# Filter-PCB.net
KiCad netlist of a schematic drawn in EAGLE
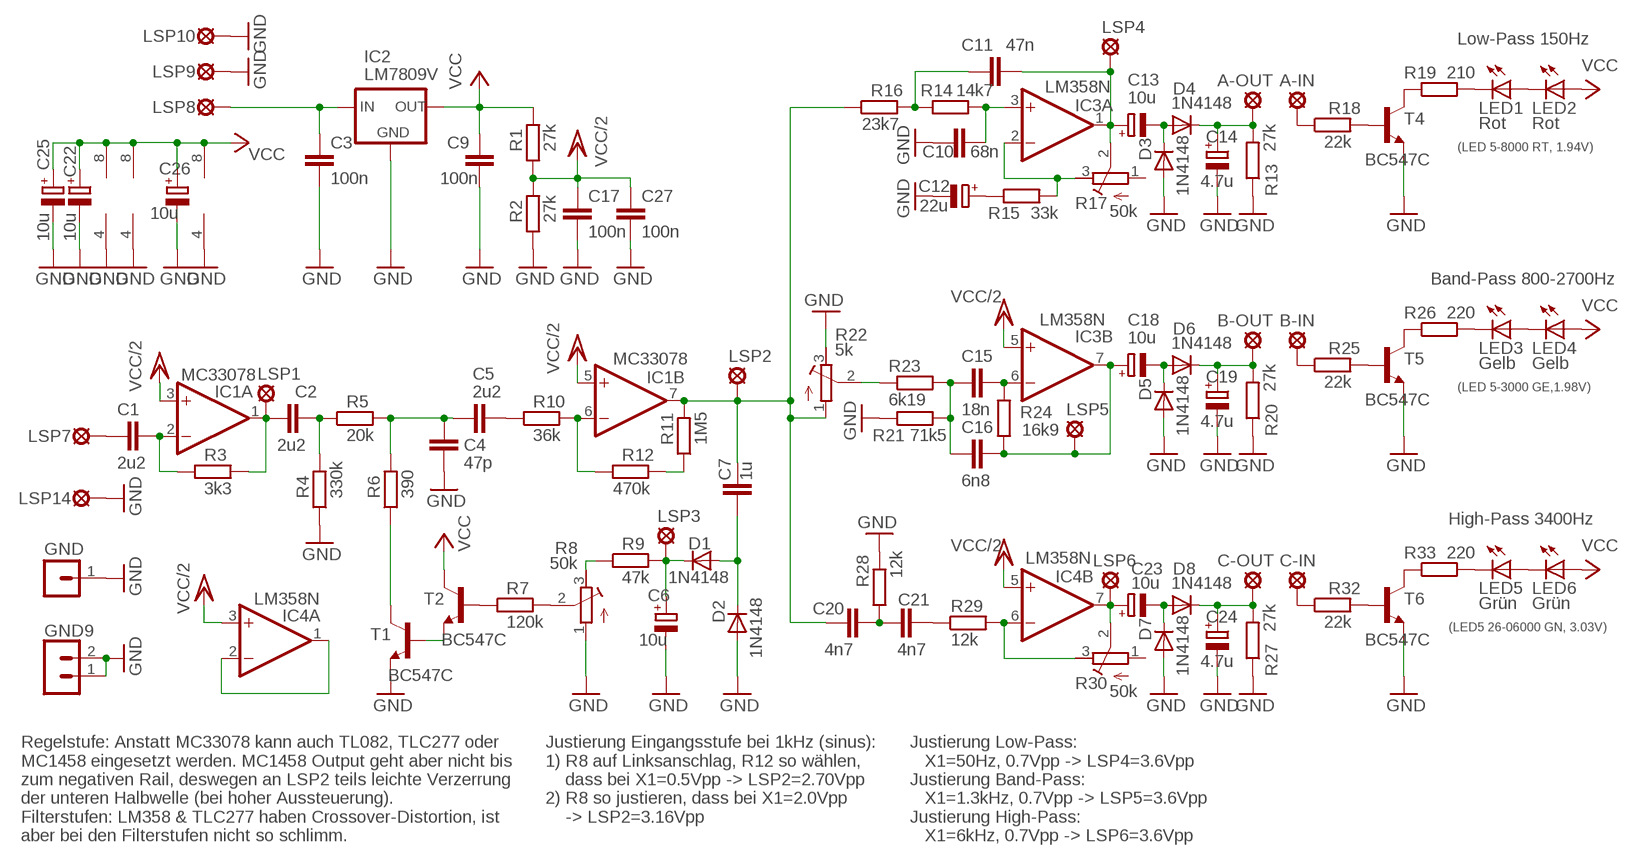
[diagram p0: schematic, sheet 1]

(export (version "E")
  (design (tool "Eeschema 10.0.6"))
  (components
    (comp (ref "A-IN")
      (value "LSP13")
      (footprint "eagle-import:LSP13")
      (libsource (lib "eagle-import") (part "LSP13"))
    )
    (comp (ref "A-OUT")
      (value "LSP13")
      (footprint "eagle-import:LSP13")
      (libsource (lib "eagle-import") (part "LSP13"))
    )
    (comp (ref "B-IN")
      (value "LSP13")
      (footprint "eagle-import:LSP13")
      (libsource (lib "eagle-import") (part "LSP13"))
    )
    (comp (ref "B-OUT")
      (value "LSP13")
      (footprint "eagle-import:LSP13")
      (libsource (lib "eagle-import") (part "LSP13"))
    )
    (comp (ref "C-IN")
      (value "LSP13")
      (footprint "eagle-import:LSP13")
      (libsource (lib "eagle-import") (part "LSP13"))
    )
    (comp (ref "C-OUT")
      (value "LSP13")
      (footprint "eagle-import:LSP13")
      (libsource (lib "eagle-import") (part "LSP13"))
    )
    (comp (ref "C1")
      (value "2u2")
      (footprint "eagle-import:C1206")
      (libsource (lib "eagle-import") (part "C-EUC1206"))
    )
    (comp (ref "C2")
      (value "2u2")
      (footprint "eagle-import:C1206")
      (libsource (lib "eagle-import") (part "C-EUC1206"))
    )
    (comp (ref "C3")
      (value "100n")
      (footprint "eagle-import:C050-024X044")
      (libsource (lib "eagle-import") (part "C-EU050-024X044"))
    )
    (comp (ref "C4")
      (value "47p")
      (footprint "eagle-import:C1206")
      (libsource (lib "eagle-import") (part "C-EUC1206"))
    )
    (comp (ref "C5")
      (value "2u2")
      (footprint "eagle-import:C1206")
      (libsource (lib "eagle-import") (part "C-EUC1206"))
    )
    (comp (ref "C6")
      (value "10u")
      (footprint "eagle-import:TT2D4")
      (libsource (lib "eagle-import") (part "CPOL-EUTT2D4"))
    )
    (comp (ref "C7")
      (value "1u")
      (footprint "eagle-import:C050-024X044")
      (libsource (lib "eagle-import") (part "C-EU050-024X044"))
    )
    (comp (ref "C9")
      (value "100n")
      (footprint "eagle-import:C1206")
      (libsource (lib "eagle-import") (part "C-EUC1206"))
    )
    (comp (ref "C10")
      (value "68n")
      (footprint "eagle-import:C1206")
      (libsource (lib "eagle-import") (part "C-EUC1206"))
    )
    (comp (ref "C11")
      (value "47n")
      (footprint "eagle-import:C1206")
      (libsource (lib "eagle-import") (part "C-EUC1206"))
    )
    (comp (ref "C12")
      (value "22u")
      (footprint "eagle-import:TT2D4")
      (libsource (lib "eagle-import") (part "CPOL-EUTT2D4"))
    )
    (comp (ref "C13")
      (value "10u")
      (footprint "eagle-import:TT2D4")
      (libsource (lib "eagle-import") (part "CPOL-EUTT2D4"))
    )
    (comp (ref "C14")
      (value "4.7u")
      (footprint "eagle-import:TT2D4")
      (libsource (lib "eagle-import") (part "CPOL-EUTT2D4"))
    )
    (comp (ref "C15")
      (value "18n")
      (footprint "eagle-import:C1206")
      (libsource (lib "eagle-import") (part "C-EUC1206"))
    )
    (comp (ref "C16")
      (value "6n8")
      (footprint "eagle-import:C1206")
      (libsource (lib "eagle-import") (part "C-EUC1206"))
    )
    (comp (ref "C17")
      (value "100n")
      (footprint "eagle-import:C050-024X044")
      (libsource (lib "eagle-import") (part "C-EU050-024X044"))
    )
    (comp (ref "C18")
      (value "10u")
      (footprint "eagle-import:TT2D4")
      (libsource (lib "eagle-import") (part "CPOL-EUTT2D4"))
    )
    (comp (ref "C19")
      (value "4.7u")
      (footprint "eagle-import:TT2D4")
      (libsource (lib "eagle-import") (part "CPOL-EUTT2D4"))
    )
    (comp (ref "C20")
      (value "4n7")
      (footprint "eagle-import:C050-024X044")
      (libsource (lib "eagle-import") (part "C-EU050-024X044"))
    )
    (comp (ref "C21")
      (value "4n7")
      (footprint "eagle-import:C050-024X044")
      (libsource (lib "eagle-import") (part "C-EU050-024X044"))
    )
    (comp (ref "C22")
      (value "10u")
      (footprint "eagle-import:TT2D4")
      (libsource (lib "eagle-import") (part "CPOL-EUTT2D4"))
    )
    (comp (ref "C23")
      (value "10u")
      (footprint "eagle-import:TT2D4")
      (libsource (lib "eagle-import") (part "CPOL-EUTT2D4"))
    )
    (comp (ref "C24")
      (value "4.7u")
      (footprint "eagle-import:TT2D4")
      (libsource (lib "eagle-import") (part "CPOL-EUTT2D4"))
    )
    (comp (ref "C25")
      (value "10u")
      (footprint "eagle-import:TT2D4")
      (libsource (lib "eagle-import") (part "CPOL-EUTT2D4"))
    )
    (comp (ref "C26")
      (value "10u")
      (footprint "eagle-import:TT2D4")
      (libsource (lib "eagle-import") (part "CPOL-EUTT2D4"))
    )
    (comp (ref "C27")
      (value "100n")
      (footprint "eagle-import:C1206")
      (libsource (lib "eagle-import") (part "C-EUC1206"))
    )
    (comp (ref "D1")
      (value "1N4148")
      (footprint "eagle-import:SOD80C")
      (libsource (lib "eagle-import") (part "DIODE-SOD80C"))
    )
    (comp (ref "D2")
      (value "1N4148")
      (footprint "eagle-import:SOD80C")
      (libsource (lib "eagle-import") (part "DIODE-SOD80C"))
    )
    (comp (ref "D3")
      (value "1N4148")
      (footprint "eagle-import:SOD80C")
      (libsource (lib "eagle-import") (part "DIODE-SOD80C"))
    )
    (comp (ref "D4")
      (value "1N4148")
      (footprint "eagle-import:SOD80C")
      (libsource (lib "eagle-import") (part "DIODE-SOD80C"))
    )
    (comp (ref "D5")
      (value "1N4148")
      (footprint "eagle-import:SOD80C")
      (libsource (lib "eagle-import") (part "DIODE-SOD80C"))
    )
    (comp (ref "D6")
      (value "1N4148")
      (footprint "eagle-import:SOD80C")
      (libsource (lib "eagle-import") (part "DIODE-SOD80C"))
    )
    (comp (ref "D7")
      (value "1N4148")
      (footprint "eagle-import:SOD80C")
      (libsource (lib "eagle-import") (part "DIODE-SOD80C"))
    )
    (comp (ref "D8")
      (value "1N4148")
      (footprint "eagle-import:SOD80C")
      (libsource (lib "eagle-import") (part "DIODE-SOD80C"))
    )
    (comp (ref "GND")
      (value "MA01-1")
      (footprint "eagle-import:MA01-1")
      (libsource (lib "eagle-import") (part "MA01-1"))
    )
    (comp (ref "GND9")
      (value "MA02-1")
      (footprint "eagle-import:MA02-1")
      (libsource (lib "eagle-import") (part "MA02-1"))
    )
    (comp (ref "IC1")
      (value "MC33078")
      (footprint "eagle-import:DIL08")
      (libsource (lib "eagle-import") (part "LM358N"))
    )
    (comp (ref "IC2")
      (value "LM7809V")
      (footprint "eagle-import:78XXS")
      (libsource (lib "eagle-import") (part "78XXS"))
    )
    (comp (ref "IC3")
      (value "LM358N")
      (footprint "eagle-import:DIL08")
      (libsource (lib "eagle-import") (part "LM358N"))
    )
    (comp (ref "IC4")
      (value "LM358N")
      (footprint "eagle-import:DIL08")
      (libsource (lib "eagle-import") (part "LM358N"))
    )
    (comp (ref "LED1")
      (value "Rot")
      (footprint "eagle-import:LED5MM")
      (libsource (lib "eagle-import") (part "LED5MM"))
    )
    (comp (ref "LED2")
      (value "Rot")
      (footprint "eagle-import:LED5MM")
      (libsource (lib "eagle-import") (part "LED5MM"))
    )
    (comp (ref "LED3")
      (value "Gelb")
      (footprint "eagle-import:LED5MM")
      (libsource (lib "eagle-import") (part "LED5MM"))
    )
    (comp (ref "LED4")
      (value "Gelb")
      (footprint "eagle-import:LED5MM")
      (libsource (lib "eagle-import") (part "LED5MM"))
    )
    (comp (ref "LED5")
      (value "Grün")
      (footprint "eagle-import:LED5MM")
      (libsource (lib "eagle-import") (part "LED5MM"))
    )
    (comp (ref "LED6")
      (value "Grün")
      (footprint "eagle-import:LED5MM")
      (libsource (lib "eagle-import") (part "LED5MM"))
    )
    (comp (ref "LSP1")
      (value "LSP11")
      (footprint "eagle-import:LSP11")
      (libsource (lib "eagle-import") (part "LSP11"))
    )
    (comp (ref "LSP2")
      (value "LSP11")
      (footprint "eagle-import:LSP11")
      (libsource (lib "eagle-import") (part "LSP11"))
    )
    (comp (ref "LSP3")
      (value "LSP11")
      (footprint "eagle-import:LSP11")
      (libsource (lib "eagle-import") (part "LSP11"))
    )
    (comp (ref "LSP4")
      (value "LSP11")
      (footprint "eagle-import:LSP11")
      (libsource (lib "eagle-import") (part "LSP11"))
    )
    (comp (ref "LSP5")
      (value "LSP11")
      (footprint "eagle-import:LSP11")
      (libsource (lib "eagle-import") (part "LSP11"))
    )
    (comp (ref "LSP6")
      (value "LSP11")
      (footprint "eagle-import:LSP11")
      (libsource (lib "eagle-import") (part "LSP11"))
    )
    (comp (ref "LSP7")
      (value "LSP13")
      (footprint "eagle-import:LSP13")
      (libsource (lib "eagle-import") (part "LSP13"))
    )
    (comp (ref "LSP8")
      (value "LSP13")
      (footprint "eagle-import:LSP13")
      (libsource (lib "eagle-import") (part "LSP13"))
    )
    (comp (ref "LSP9")
      (value "LSP13")
      (footprint "eagle-import:LSP13")
      (libsource (lib "eagle-import") (part "LSP13"))
    )
    (comp (ref "LSP10")
      (value "LSP13")
      (footprint "eagle-import:LSP13")
      (libsource (lib "eagle-import") (part "LSP13"))
    )
    (comp (ref "LSP14")
      (value "LSP13")
      (footprint "eagle-import:LSP13")
      (libsource (lib "eagle-import") (part "LSP13"))
    )
    (comp (ref "R1")
      (value "27k")
      (footprint "eagle-import:M1206")
      (libsource (lib "eagle-import") (part "R-EU_M1206"))
    )
    (comp (ref "R2")
      (value "27k")
      (footprint "eagle-import:M1206")
      (libsource (lib "eagle-import") (part "R-EU_M1206"))
    )
    (comp (ref "R3")
      (value "3k3")
      (footprint "eagle-import:M1206")
      (libsource (lib "eagle-import") (part "R-EU_M1206"))
    )
    (comp (ref "R4")
      (value "330k")
      (footprint "eagle-import:M1206")
      (libsource (lib "eagle-import") (part "R-EU_M1206"))
    )
    (comp (ref "R5")
      (value "20k")
      (footprint "eagle-import:M1206")
      (libsource (lib "eagle-import") (part "R-EU_M1206"))
    )
    (comp (ref "R6")
      (value "390")
      (footprint "eagle-import:M1206")
      (libsource (lib "eagle-import") (part "R-EU_M1206"))
    )
    (comp (ref "R7")
      (value "120k")
      (footprint "eagle-import:M1206")
      (libsource (lib "eagle-import") (part "R-EU_M1206"))
    )
    (comp (ref "R8")
      (value "50k")
      (footprint "eagle-import:RTRIM64P")
      (libsource (lib "eagle-import") (part "R-TRIMM64P"))
    )
    (comp (ref "R9")
      (value "47k")
      (footprint "eagle-import:M1206")
      (libsource (lib "eagle-import") (part "R-EU_M1206"))
    )
    (comp (ref "R10")
      (value "36k")
      (footprint "eagle-import:M1206")
      (libsource (lib "eagle-import") (part "R-EU_M1206"))
    )
    (comp (ref "R11")
      (value "1M5")
      (footprint "eagle-import:M1206")
      (libsource (lib "eagle-import") (part "R-EU_M1206"))
    )
    (comp (ref "R12")
      (value "470k")
      (footprint "eagle-import:0207_10")
      (libsource (lib "eagle-import") (part "R-EU_0207/10"))
    )
    (comp (ref "R13")
      (value "27k")
      (footprint "eagle-import:0207_10")
      (libsource (lib "eagle-import") (part "R-EU_0207/10"))
    )
    (comp (ref "R14")
      (value "14k7")
      (footprint "eagle-import:0207_10")
      (libsource (lib "eagle-import") (part "R-EU_0207/10"))
    )
    (comp (ref "R15")
      (value "33k")
      (footprint "eagle-import:M1206")
      (libsource (lib "eagle-import") (part "R-EU_M1206"))
    )
    (comp (ref "R16")
      (value "23k7")
      (footprint "eagle-import:0207_10")
      (libsource (lib "eagle-import") (part "R-EU_0207/10"))
    )
    (comp (ref "R17")
      (value "50k")
      (footprint "eagle-import:RTRIM64P")
      (libsource (lib "eagle-import") (part "R-TRIMM64P"))
    )
    (comp (ref "R18")
      (value "22k")
      (footprint "eagle-import:M1206")
      (libsource (lib "eagle-import") (part "R-EU_M1206"))
    )
    (comp (ref "R19")
      (value "210")
      (footprint "eagle-import:0207_10")
      (libsource (lib "eagle-import") (part "R-EU_0207/10"))
    )
    (comp (ref "R20")
      (value "27k")
      (footprint "eagle-import:0207_10")
      (libsource (lib "eagle-import") (part "R-EU_0207/10"))
    )
    (comp (ref "R21")
      (value "71k5")
      (footprint "eagle-import:0207_10")
      (libsource (lib "eagle-import") (part "R-EU_0207/10"))
    )
    (comp (ref "R22")
      (value "5k")
      (footprint "eagle-import:RTRIM64P")
      (libsource (lib "eagle-import") (part "R-TRIMM64P"))
    )
    (comp (ref "R23")
      (value "6k19")
      (footprint "eagle-import:0207_10")
      (libsource (lib "eagle-import") (part "R-EU_0207/10"))
    )
    (comp (ref "R24")
      (value "16k9")
      (footprint "eagle-import:0207_10")
      (libsource (lib "eagle-import") (part "R-EU_0207/10"))
    )
    (comp (ref "R25")
      (value "22k")
      (footprint "eagle-import:M1206")
      (libsource (lib "eagle-import") (part "R-EU_M1206"))
    )
    (comp (ref "R26")
      (value "220")
      (footprint "eagle-import:0207_10")
      (libsource (lib "eagle-import") (part "R-EU_0207/10"))
    )
    (comp (ref "R27")
      (value "27k")
      (footprint "eagle-import:0207_10")
      (libsource (lib "eagle-import") (part "R-EU_0207/10"))
    )
    (comp (ref "R28")
      (value "12k")
      (footprint "eagle-import:0207_10")
      (libsource (lib "eagle-import") (part "R-EU_0207/10"))
    )
    (comp (ref "R29")
      (value "12k")
      (footprint "eagle-import:0207_10")
      (libsource (lib "eagle-import") (part "R-EU_0207/10"))
    )
    (comp (ref "R30")
      (value "50k")
      (footprint "eagle-import:RTRIM64P")
      (libsource (lib "eagle-import") (part "R-TRIMM64P"))
    )
    (comp (ref "R32")
      (value "22k")
      (footprint "eagle-import:M1206")
      (libsource (lib "eagle-import") (part "R-EU_M1206"))
    )
    (comp (ref "R33")
      (value "220")
      (footprint "eagle-import:0207_10")
      (libsource (lib "eagle-import") (part "R-EU_0207/10"))
    )
    (comp (ref "T1")
      (value "BC547C")
      (footprint "eagle-import:TO92")
      (libsource (lib "eagle-import") (part "BC547"))
    )
    (comp (ref "T2")
      (value "BC547C")
      (footprint "eagle-import:TO92")
      (libsource (lib "eagle-import") (part "BC547"))
    )
    (comp (ref "T4")
      (value "BC547C")
      (footprint "eagle-import:TO92")
      (libsource (lib "eagle-import") (part "BC547"))
    )
    (comp (ref "T5")
      (value "BC547C")
      (footprint "eagle-import:TO92")
      (libsource (lib "eagle-import") (part "BC547"))
    )
    (comp (ref "T6")
      (value "BC547C")
      (footprint "eagle-import:TO92")
      (libsource (lib "eagle-import") (part "BC547"))
    )
  )
  (nets
    (net (code "1") (name "GND") (class "Default")
      (node (ref "C10") (pin "1") (pinfunction "1_1") (pintype "passive"))
      (node (ref "C12") (pin "-") (pinfunction "-_-") (pintype "passive"))
      (node (ref "C14") (pin "-") (pinfunction "-_-") (pintype "passive"))
      (node (ref "C17") (pin "2") (pinfunction "2_2") (pintype "passive"))
      (node (ref "C19") (pin "-") (pinfunction "-_-") (pintype "passive"))
      (node (ref "C22") (pin "-") (pinfunction "-_-") (pintype "passive"))
      (node (ref "C24") (pin "-") (pinfunction "-_-") (pintype "passive"))
      (node (ref "C25") (pin "-") (pinfunction "-_-") (pintype "passive"))
      (node (ref "C26") (pin "-") (pinfunction "-_-") (pintype "passive"))
      (node (ref "C27") (pin "2") (pinfunction "2_2") (pintype "passive"))
      (node (ref "C3") (pin "2") (pinfunction "2_2") (pintype "passive"))
      (node (ref "C4") (pin "2") (pinfunction "2_2") (pintype "passive"))
      (node (ref "C6") (pin "-") (pinfunction "-_-") (pintype "passive"))
      (node (ref "C9") (pin "1") (pinfunction "1_1") (pintype "passive"))
      (node (ref "D2") (pin "A") (pinfunction "A_A") (pintype "passive"))
      (node (ref "D3") (pin "A") (pinfunction "A_A") (pintype "passive"))
      (node (ref "D5") (pin "A") (pinfunction "A_A") (pintype "passive"))
      (node (ref "D7") (pin "A") (pinfunction "A_A") (pintype "passive"))
      (node (ref "GND") (pin "1") (pinfunction "1_1") (pintype "passive"))
      (node (ref "GND9") (pin "1") (pinfunction "1_1") (pintype "passive"))
      (node (ref "GND9") (pin "2") (pinfunction "2_2") (pintype "passive"))
      (node (ref "IC1") (pin "4") (pinfunction "V-_4") (pintype "power_in"))
      (node (ref "IC2") (pin "GND") (pinfunction "GND_GND") (pintype "input"))
      (node (ref "IC3") (pin "4") (pinfunction "V-_4") (pintype "power_in"))
      (node (ref "IC4") (pin "4") (pinfunction "V-_4") (pintype "power_in"))
      (node (ref "LSP10") (pin "MP") (pinfunction "MP_MP") (pintype "passive"))
      (node (ref "LSP14") (pin "MP") (pinfunction "MP_MP") (pintype "passive"))
      (node (ref "LSP9") (pin "MP") (pinfunction "MP_MP") (pintype "passive"))
      (node (ref "R13") (pin "1") (pinfunction "1_1") (pintype "passive"))
      (node (ref "R2") (pin "1") (pinfunction "1_1") (pintype "passive"))
      (node (ref "R20") (pin "1") (pinfunction "1_1") (pintype "passive"))
      (node (ref "R21") (pin "1") (pinfunction "1_1") (pintype "passive"))
      (node (ref "R22") (pin "3") (pinfunction "E_3") (pintype "passive"))
      (node (ref "R27") (pin "1") (pinfunction "1_1") (pintype "passive"))
      (node (ref "R28") (pin "2") (pinfunction "2_2") (pintype "passive"))
      (node (ref "R4") (pin "1") (pinfunction "1_1") (pintype "passive"))
      (node (ref "R8") (pin "1") (pinfunction "A_1") (pintype "passive"))
      (node (ref "T1") (pin "1") (pinfunction "E_1") (pintype "passive"))
      (node (ref "T4") (pin "1") (pinfunction "E_1") (pintype "passive"))
      (node (ref "T5") (pin "1") (pinfunction "E_1") (pintype "passive"))
      (node (ref "T6") (pin "1") (pinfunction "E_1") (pintype "passive"))
    )
    (net (code "2") (name "Net-(A-IN-PadMP)") (class "Default")
      (node (ref "A-IN") (pin "MP") (pinfunction "MP_MP") (pintype "passive"))
      (node (ref "R18") (pin "1") (pinfunction "1_1") (pintype "passive"))
    )
    (net (code "3") (name "Net-(A-OUT-PadMP)") (class "Default")
      (node (ref "A-OUT") (pin "MP") (pinfunction "MP_MP") (pintype "passive"))
      (node (ref "C14") (pin "+") (pinfunction "+_+") (pintype "passive"))
      (node (ref "D4") (pin "C") (pinfunction "C_C") (pintype "passive"))
      (node (ref "R13") (pin "2") (pinfunction "2_2") (pintype "passive"))
    )
    (net (code "4") (name "Net-(B-IN-PadMP)") (class "Default")
      (node (ref "B-IN") (pin "MP") (pinfunction "MP_MP") (pintype "passive"))
      (node (ref "R25") (pin "1") (pinfunction "1_1") (pintype "passive"))
    )
    (net (code "5") (name "Net-(B-OUT-PadMP)") (class "Default")
      (node (ref "B-OUT") (pin "MP") (pinfunction "MP_MP") (pintype "passive"))
      (node (ref "C19") (pin "+") (pinfunction "+_+") (pintype "passive"))
      (node (ref "D6") (pin "C") (pinfunction "C_C") (pintype "passive"))
      (node (ref "R20") (pin "2") (pinfunction "2_2") (pintype "passive"))
    )
    (net (code "6") (name "Net-(C-IN-PadMP)") (class "Default")
      (node (ref "C-IN") (pin "MP") (pinfunction "MP_MP") (pintype "passive"))
      (node (ref "R32") (pin "1") (pinfunction "1_1") (pintype "passive"))
    )
    (net (code "7") (name "Net-(C-OUT-PadMP)") (class "Default")
      (node (ref "C-OUT") (pin "MP") (pinfunction "MP_MP") (pintype "passive"))
      (node (ref "C24") (pin "+") (pinfunction "+_+") (pintype "passive"))
      (node (ref "D8") (pin "C") (pinfunction "C_C") (pintype "passive"))
      (node (ref "R27") (pin "2") (pinfunction "2_2") (pintype "passive"))
    )
    (net (code "8") (name "Net-(C1-Pad1)") (class "Default")
      (node (ref "C1") (pin "1") (pinfunction "1_1") (pintype "passive"))
      (node (ref "LSP7") (pin "MP") (pinfunction "MP_MP") (pintype "passive"))
    )
    (net (code "9") (name "Net-(C2-Pad2)") (class "Default")
      (node (ref "C2") (pin "2") (pinfunction "2_2") (pintype "passive"))
      (node (ref "R4") (pin "2") (pinfunction "2_2") (pintype "passive"))
      (node (ref "R5") (pin "1") (pinfunction "1_1") (pintype "passive"))
    )
    (net (code "10") (name "Net-(C3-Pad1)") (class "Default")
      (node (ref "C3") (pin "1") (pinfunction "1_1") (pintype "passive"))
      (node (ref "IC2") (pin "IN") (pinfunction "IN_IN") (pintype "input"))
      (node (ref "LSP8") (pin "MP") (pinfunction "MP_MP") (pintype "passive"))
    )
    (net (code "11") (name "Net-(C4-Pad1)") (class "Default")
      (node (ref "C4") (pin "1") (pinfunction "1_1") (pintype "passive"))
      (node (ref "C5") (pin "1") (pinfunction "1_1") (pintype "passive"))
      (node (ref "R5") (pin "2") (pinfunction "2_2") (pintype "passive"))
      (node (ref "R6") (pin "2") (pinfunction "2_2") (pintype "passive"))
    )
    (net (code "12") (name "Net-(C5-Pad2)") (class "Default")
      (node (ref "C5") (pin "2") (pinfunction "2_2") (pintype "passive"))
      (node (ref "R10") (pin "1") (pinfunction "1_1") (pintype "passive"))
    )
    (net (code "13") (name "Net-(C6-Pad+)") (class "Default")
      (node (ref "C6") (pin "+") (pinfunction "+_+") (pintype "passive"))
      (node (ref "D1") (pin "C") (pinfunction "C_C") (pintype "passive"))
      (node (ref "LSP3") (pin "MP") (pinfunction "MP_MP") (pintype "passive"))
      (node (ref "R9") (pin "2") (pinfunction "2_2") (pintype "passive"))
    )
    (net (code "14") (name "Net-(C7-Pad2)") (class "Default")
      (node (ref "C7") (pin "2") (pinfunction "2_2") (pintype "passive"))
      (node (ref "D1") (pin "A") (pinfunction "A_A") (pintype "passive"))
      (node (ref "D2") (pin "C") (pinfunction "C_C") (pintype "passive"))
    )
    (net (code "15") (name "Net-(C11-Pad1)") (class "Default")
      (node (ref "C11") (pin "1") (pinfunction "1_1") (pintype "passive"))
      (node (ref "R14") (pin "1") (pinfunction "1_1") (pintype "passive"))
      (node (ref "R16") (pin "2") (pinfunction "2_2") (pintype "passive"))
    )
    (net (code "16") (name "Net-(C12-Pad+)") (class "Default")
      (node (ref "C12") (pin "+") (pinfunction "+_+") (pintype "passive"))
      (node (ref "R15") (pin "1") (pinfunction "1_1") (pintype "passive"))
    )
    (net (code "17") (name "Net-(C13-Pad-)") (class "Default")
      (node (ref "C13") (pin "-") (pinfunction "-_-") (pintype "passive"))
      (node (ref "D3") (pin "C") (pinfunction "C_C") (pintype "passive"))
      (node (ref "D4") (pin "A") (pinfunction "A_A") (pintype "passive"))
    )
    (net (code "18") (name "Net-(C15-Pad1)") (class "Default")
      (node (ref "C15") (pin "1") (pinfunction "1_1") (pintype "passive"))
      (node (ref "C16") (pin "1") (pinfunction "1_1") (pintype "passive"))
      (node (ref "R21") (pin "2") (pinfunction "2_2") (pintype "passive"))
      (node (ref "R23") (pin "2") (pinfunction "2_2") (pintype "passive"))
    )
    (net (code "19") (name "Net-(C18-Pad-)") (class "Default")
      (node (ref "C18") (pin "-") (pinfunction "-_-") (pintype "passive"))
      (node (ref "D5") (pin "C") (pinfunction "C_C") (pintype "passive"))
      (node (ref "D6") (pin "A") (pinfunction "A_A") (pintype "passive"))
    )
    (net (code "20") (name "Net-(C20-Pad2)") (class "Default")
      (node (ref "C20") (pin "2") (pinfunction "2_2") (pintype "passive"))
      (node (ref "C21") (pin "1") (pinfunction "1_1") (pintype "passive"))
      (node (ref "R28") (pin "1") (pinfunction "1_1") (pintype "passive"))
    )
    (net (code "21") (name "Net-(C21-Pad2)") (class "Default")
      (node (ref "C21") (pin "2") (pinfunction "2_2") (pintype "passive"))
      (node (ref "R29") (pin "1") (pinfunction "1_1") (pintype "passive"))
    )
    (net (code "22") (name "Net-(C23-Pad-)") (class "Default")
      (node (ref "C23") (pin "-") (pinfunction "-_-") (pintype "passive"))
      (node (ref "D7") (pin "C") (pinfunction "C_C") (pintype "passive"))
      (node (ref "D8") (pin "A") (pinfunction "A_A") (pintype "passive"))
    )
    (net (code "23") (name "Net-(IC1A--IN)") (class "Default")
      (node (ref "C1") (pin "2") (pinfunction "2_2") (pintype "passive"))
      (node (ref "IC1") (pin "2") (pinfunction "-IN_2") (pintype "input"))
      (node (ref "R3") (pin "1") (pinfunction "1_1") (pintype "passive"))
    )
    (net (code "24") (name "Net-(IC1A-OUT)") (class "Default")
      (node (ref "C2") (pin "1") (pinfunction "1_1") (pintype "passive"))
      (node (ref "IC1") (pin "1") (pinfunction "OUT_1") (pintype "output"))
      (node (ref "LSP1") (pin "MP") (pinfunction "MP_MP") (pintype "passive"))
      (node (ref "R3") (pin "2") (pinfunction "2_2") (pintype "passive"))
    )
    (net (code "25") (name "Net-(IC1B--IN)") (class "Default")
      (node (ref "IC1") (pin "6") (pinfunction "-IN_6") (pintype "input"))
      (node (ref "R10") (pin "2") (pinfunction "2_2") (pintype "passive"))
      (node (ref "R12") (pin "1") (pinfunction "1_1") (pintype "passive"))
    )
    (net (code "26") (name "Net-(IC1B-OUT)") (class "Default")
      (node (ref "C20") (pin "1") (pinfunction "1_1") (pintype "passive"))
      (node (ref "C7") (pin "1") (pinfunction "1_1") (pintype "passive"))
      (node (ref "IC1") (pin "7") (pinfunction "OUT_7") (pintype "output"))
      (node (ref "LSP2") (pin "MP") (pinfunction "MP_MP") (pintype "passive"))
      (node (ref "R11") (pin "2") (pinfunction "2_2") (pintype "passive"))
      (node (ref "R16") (pin "1") (pinfunction "1_1") (pintype "passive"))
      (node (ref "R22") (pin "1") (pinfunction "A_1") (pintype "passive"))
    )
    (net (code "27") (name "Net-(IC3A-+IN)") (class "Default")
      (node (ref "C10") (pin "2") (pinfunction "2_2") (pintype "passive"))
      (node (ref "IC3") (pin "3") (pinfunction "+IN_3") (pintype "input"))
      (node (ref "R14") (pin "2") (pinfunction "2_2") (pintype "passive"))
    )
    (net (code "28") (name "Net-(IC3A--IN)") (class "Default")
      (node (ref "IC3") (pin "2") (pinfunction "-IN_2") (pintype "input"))
      (node (ref "R15") (pin "2") (pinfunction "2_2") (pintype "passive"))
      (node (ref "R17") (pin "3") (pinfunction "E_3") (pintype "passive"))
    )
    (net (code "29") (name "Net-(IC3A-OUT)") (class "Default")
      (node (ref "C11") (pin "2") (pinfunction "2_2") (pintype "passive"))
      (node (ref "C13") (pin "+") (pinfunction "+_+") (pintype "passive"))
      (node (ref "IC3") (pin "1") (pinfunction "OUT_1") (pintype "output"))
      (node (ref "LSP4") (pin "MP") (pinfunction "MP_MP") (pintype "passive"))
      (node (ref "R17") (pin "2") (pinfunction "S_2") (pintype "passive"))
    )
    (net (code "30") (name "Net-(IC3B--IN)") (class "Default")
      (node (ref "C15") (pin "2") (pinfunction "2_2") (pintype "passive"))
      (node (ref "IC3") (pin "6") (pinfunction "-IN_6") (pintype "input"))
      (node (ref "R24") (pin "2") (pinfunction "2_2") (pintype "passive"))
    )
    (net (code "31") (name "Net-(IC3B-OUT)") (class "Default")
      (node (ref "C16") (pin "2") (pinfunction "2_2") (pintype "passive"))
      (node (ref "C18") (pin "+") (pinfunction "+_+") (pintype "passive"))
      (node (ref "IC3") (pin "7") (pinfunction "OUT_7") (pintype "output"))
      (node (ref "LSP5") (pin "MP") (pinfunction "MP_MP") (pintype "passive"))
      (node (ref "R24") (pin "1") (pinfunction "1_1") (pintype "passive"))
    )
    (net (code "32") (name "Net-(IC4A--IN)") (class "Default")
      (node (ref "IC4") (pin "1") (pinfunction "OUT_1") (pintype "output"))
      (node (ref "IC4") (pin "2") (pinfunction "-IN_2") (pintype "input"))
    )
    (net (code "33") (name "Net-(IC4B--IN)") (class "Default")
      (node (ref "IC4") (pin "6") (pinfunction "-IN_6") (pintype "input"))
      (node (ref "R29") (pin "2") (pinfunction "2_2") (pintype "passive"))
      (node (ref "R30") (pin "3") (pinfunction "E_3") (pintype "passive"))
    )
    (net (code "34") (name "Net-(IC4B-OUT)") (class "Default")
      (node (ref "C23") (pin "+") (pinfunction "+_+") (pintype "passive"))
      (node (ref "IC4") (pin "7") (pinfunction "OUT_7") (pintype "output"))
      (node (ref "LSP6") (pin "MP") (pinfunction "MP_MP") (pintype "passive"))
      (node (ref "R30") (pin "2") (pinfunction "S_2") (pintype "passive"))
    )
    (net (code "35") (name "Net-(LED1-C)") (class "Default")
      (node (ref "LED1") (pin "K") (pinfunction "C_K") (pintype "passive"))
      (node (ref "R19") (pin "2") (pinfunction "2_2") (pintype "passive"))
    )
    (net (code "36") (name "Net-(LED2-C)") (class "Default")
      (node (ref "LED1") (pin "A") (pinfunction "A_A") (pintype "passive"))
      (node (ref "LED2") (pin "K") (pinfunction "C_K") (pintype "passive"))
    )
    (net (code "37") (name "Net-(LED3-C)") (class "Default")
      (node (ref "LED3") (pin "K") (pinfunction "C_K") (pintype "passive"))
      (node (ref "R26") (pin "2") (pinfunction "2_2") (pintype "passive"))
    )
    (net (code "38") (name "Net-(LED4-C)") (class "Default")
      (node (ref "LED3") (pin "A") (pinfunction "A_A") (pintype "passive"))
      (node (ref "LED4") (pin "K") (pinfunction "C_K") (pintype "passive"))
    )
    (net (code "39") (name "Net-(LED5-C)") (class "Default")
      (node (ref "LED5") (pin "K") (pinfunction "C_K") (pintype "passive"))
      (node (ref "R33") (pin "2") (pinfunction "2_2") (pintype "passive"))
    )
    (net (code "40") (name "Net-(LED6-C)") (class "Default")
      (node (ref "LED5") (pin "A") (pinfunction "A_A") (pintype "passive"))
      (node (ref "LED6") (pin "K") (pinfunction "C_K") (pintype "passive"))
    )
    (net (code "41") (name "Net-(R8-E)") (class "Default")
      (node (ref "R8") (pin "3") (pinfunction "E_3") (pintype "passive"))
      (node (ref "R9") (pin "1") (pinfunction "1_1") (pintype "passive"))
    )
    (net (code "42") (name "Net-(R8-S)") (class "Default")
      (node (ref "R7") (pin "2") (pinfunction "2_2") (pintype "passive"))
      (node (ref "R8") (pin "2") (pinfunction "S_2") (pintype "passive"))
    )
    (net (code "43") (name "Net-(R11-Pad1)") (class "Default")
      (node (ref "R11") (pin "1") (pinfunction "1_1") (pintype "passive"))
      (node (ref "R12") (pin "2") (pinfunction "2_2") (pintype "passive"))
    )
    (net (code "44") (name "Net-(R22-S)") (class "Default")
      (node (ref "R22") (pin "2") (pinfunction "S_2") (pintype "passive"))
      (node (ref "R23") (pin "1") (pinfunction "1_1") (pintype "passive"))
    )
    (net (code "45") (name "Net-(T1-B)") (class "Default")
      (node (ref "T1") (pin "2") (pinfunction "B_2") (pintype "passive"))
      (node (ref "T2") (pin "1") (pinfunction "E_1") (pintype "passive"))
    )
    (net (code "46") (name "Net-(T1-C)") (class "Default")
      (node (ref "R6") (pin "1") (pinfunction "1_1") (pintype "passive"))
      (node (ref "T1") (pin "3") (pinfunction "C_3") (pintype "passive"))
    )
    (net (code "47") (name "Net-(T2-B)") (class "Default")
      (node (ref "R7") (pin "1") (pinfunction "1_1") (pintype "passive"))
      (node (ref "T2") (pin "2") (pinfunction "B_2") (pintype "passive"))
    )
    (net (code "48") (name "Net-(T4-B)") (class "Default")
      (node (ref "R18") (pin "2") (pinfunction "2_2") (pintype "passive"))
      (node (ref "T4") (pin "2") (pinfunction "B_2") (pintype "passive"))
    )
    (net (code "49") (name "Net-(T4-C)") (class "Default")
      (node (ref "R19") (pin "1") (pinfunction "1_1") (pintype "passive"))
      (node (ref "T4") (pin "3") (pinfunction "C_3") (pintype "passive"))
    )
    (net (code "50") (name "Net-(T5-B)") (class "Default")
      (node (ref "R25") (pin "2") (pinfunction "2_2") (pintype "passive"))
      (node (ref "T5") (pin "2") (pinfunction "B_2") (pintype "passive"))
    )
    (net (code "51") (name "Net-(T5-C)") (class "Default")
      (node (ref "R26") (pin "1") (pinfunction "1_1") (pintype "passive"))
      (node (ref "T5") (pin "3") (pinfunction "C_3") (pintype "passive"))
    )
    (net (code "52") (name "Net-(T6-B)") (class "Default")
      (node (ref "R32") (pin "2") (pinfunction "2_2") (pintype "passive"))
      (node (ref "T6") (pin "2") (pinfunction "B_2") (pintype "passive"))
    )
    (net (code "53") (name "Net-(T6-C)") (class "Default")
      (node (ref "R33") (pin "1") (pinfunction "1_1") (pintype "passive"))
      (node (ref "T6") (pin "3") (pinfunction "C_3") (pintype "passive"))
    )
    (net (code "54") (name "VCC") (class "Default")
      (node (ref "C22") (pin "+") (pinfunction "+_+") (pintype "passive"))
      (node (ref "C25") (pin "+") (pinfunction "+_+") (pintype "passive"))
      (node (ref "C26") (pin "+") (pinfunction "+_+") (pintype "passive"))
      (node (ref "C9") (pin "2") (pinfunction "2_2") (pintype "passive"))
      (node (ref "IC1") (pin "8") (pinfunction "V+_8") (pintype "power_in"))
      (node (ref "IC2") (pin "OUT") (pinfunction "OUT_OUT") (pintype "passive"))
      (node (ref "IC3") (pin "8") (pinfunction "V+_8") (pintype "power_in"))
      (node (ref "IC4") (pin "8") (pinfunction "V+_8") (pintype "power_in"))
      (node (ref "LED2") (pin "A") (pinfunction "A_A") (pintype "passive"))
      (node (ref "LED4") (pin "A") (pinfunction "A_A") (pintype "passive"))
      (node (ref "LED6") (pin "A") (pinfunction "A_A") (pintype "passive"))
      (node (ref "R1") (pin "2") (pinfunction "2_2") (pintype "passive"))
      (node (ref "T2") (pin "3") (pinfunction "C_3") (pintype "passive"))
    )
    (net (code "55") (name "VCC{slash}2") (class "Default")
      (node (ref "C17") (pin "1") (pinfunction "1_1") (pintype "passive"))
      (node (ref "C27") (pin "1") (pinfunction "1_1") (pintype "passive"))
      (node (ref "IC1") (pin "3") (pinfunction "+IN_3") (pintype "input"))
      (node (ref "IC1") (pin "5") (pinfunction "+IN_5") (pintype "input"))
      (node (ref "IC3") (pin "5") (pinfunction "+IN_5") (pintype "input"))
      (node (ref "IC4") (pin "3") (pinfunction "+IN_3") (pintype "input"))
      (node (ref "IC4") (pin "5") (pinfunction "+IN_5") (pintype "input"))
      (node (ref "R1") (pin "1") (pinfunction "1_1") (pintype "passive"))
      (node (ref "R2") (pin "2") (pinfunction "2_2") (pintype "passive"))
    )
    (net (code "56") (name "unconnected-(R17-A-Pad1)") (class "Default")
      (node (ref "R17") (pin "1") (pinfunction "A_1") (pintype "passive"))
    )
    (net (code "57") (name "unconnected-(R30-A-Pad1)") (class "Default")
      (node (ref "R30") (pin "1") (pinfunction "A_1") (pintype "passive"))
    )
  )
)
